# untitled.net
KiCad netlist of a schematic drawn in EAGLE
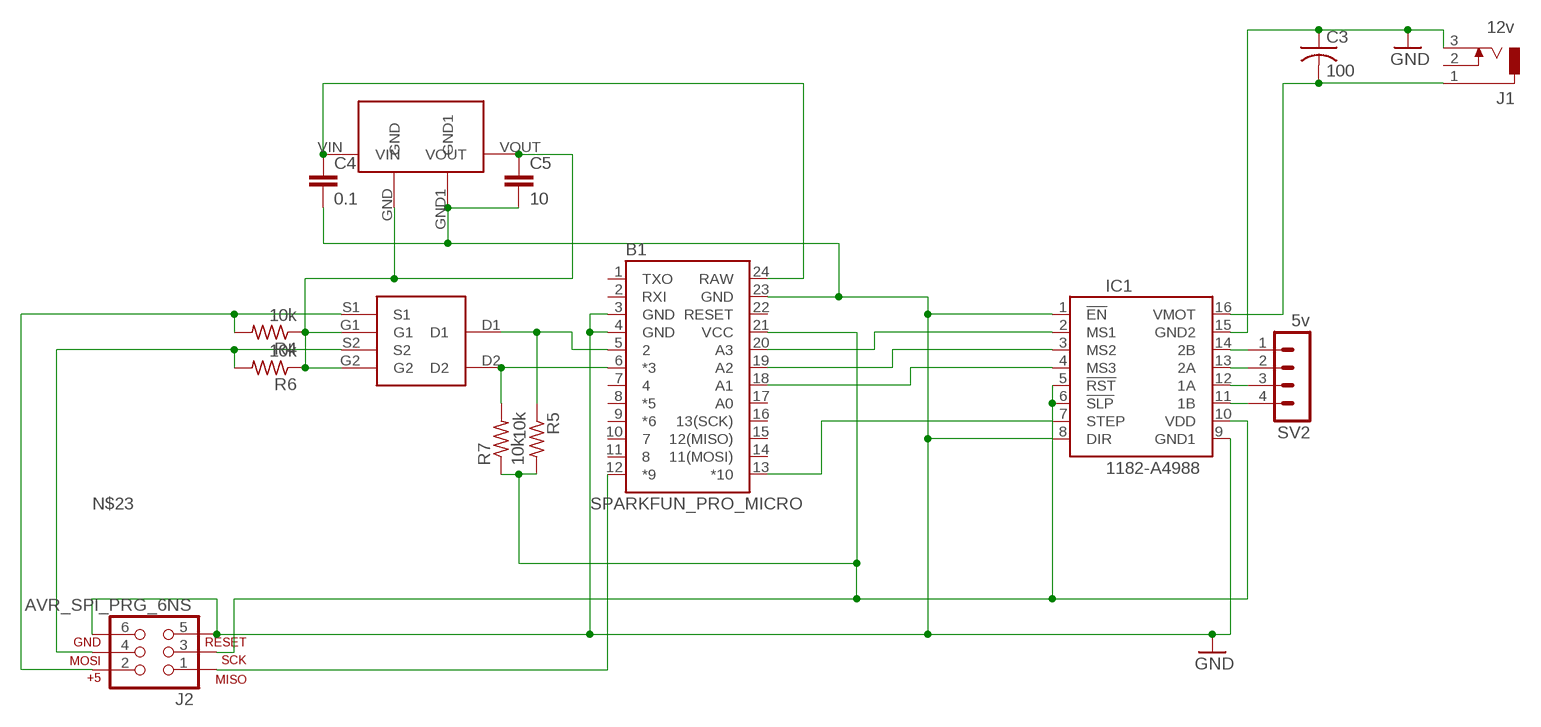
[diagram p0: schematic, sheet 1]

(export (version "E")
  (design (tool "Eeschema 10.0.6"))
  (components
    (comp (ref "B1")
      (value "SPARKFUN_PRO_MICRO")
      (footprint "eagle-import:SPARKFUN_PRO_MICRO")
      (libsource (lib "eagle-import") (part "SPARKFUN_PRO_MICRO"))
    )
    (comp (ref "C3")
      (value "100")
      (footprint "eagle-import:C050-075X075")
      (libsource (lib "eagle-import") (part "C-US050-075X075"))
    )
    (comp (ref "C4")
      (value "0.1")
      (footprint "eagle-import:0603-CAP")
      (libsource (lib "eagle-import") (part "CAP0603-CAP"))
    )
    (comp (ref "C5")
      (value "10")
      (footprint "eagle-import:0603-CAP")
      (libsource (lib "eagle-import") (part "CAP0603-CAP"))
    )
    (comp (ref "IC1")
      (value "1182-A4988")
      (footprint "eagle-import:A4988")
      (libsource (lib "eagle-import") (part "1182-A4988"))
    )
    (comp (ref "J1")
      (value "12v")
      (footprint "eagle-import:DCJ0303")
      (libsource (lib "eagle-import") (part "DCJ0303"))
    )
    (comp (ref "J2")
      (value "AVR_SPI_PRG_6NS")
      (footprint "eagle-import:2X3-NS")
      (libsource (lib "eagle-import") (part "AVR_SPI_PRG_6NS"))
    )
    (comp (ref "R4")
      (value "10k")
      (footprint "eagle-import:0207_10")
      (libsource (lib "eagle-import") (part "R-US_0207/10"))
    )
    (comp (ref "R5")
      (value "10k")
      (footprint "eagle-import:0207_10")
      (libsource (lib "eagle-import") (part "R-US_0207/10"))
    )
    (comp (ref "R6")
      (value "10k")
      (footprint "eagle-import:0207_10")
      (libsource (lib "eagle-import") (part "R-US_0207/10"))
    )
    (comp (ref "R7")
      (value "10k")
      (footprint "eagle-import:0207_10")
      (libsource (lib "eagle-import") (part "R-US_0207/10"))
    )
    (comp (ref "SV2")
      (value "5v")
      (footprint "eagle-import:MA04-1")
      (libsource (lib "eagle-import") (part "MA04-1"))
    )
    (comp (ref "U$2")
      (value "LD1117")
      (footprint "eagle-import:SOT223")
      (libsource (lib "eagle-import") (part "LD1117"))
    )
    (comp (ref "U$3")
      (value "BSS138")
      (footprint "eagle-import:SOT363")
      (libsource (lib "eagle-import") (part "BSS138"))
    )
  )
  (nets
    (net (code "1") (name "/N$23") (class "Default")
      (node (ref "J2") (pin "4") (pinfunction "4_4") (pintype "passive"))
      (node (ref "R6") (pin "2") (pinfunction "2_2") (pintype "passive"))
      (node (ref "U$3") (pin "S2") (pinfunction "S2_S2") (pintype "bidirectional"))
    )
    (net (code "2") (name "GND") (class "Default")
      (node (ref "B1") (pin "23") (pinfunction "GND_23") (pintype "power_in"))
      (node (ref "B1") (pin "3") (pinfunction "GND_3") (pintype "power_in"))
      (node (ref "B1") (pin "4") (pinfunction "GND_4") (pintype "power_in"))
      (node (ref "C3") (pin "1") (pinfunction "1_1") (pintype "passive"))
      (node (ref "C4") (pin "2") (pinfunction "2_2") (pintype "passive"))
      (node (ref "C5") (pin "2") (pinfunction "2_2") (pintype "passive"))
      (node (ref "IC1") (pin "1") (pinfunction "~{EN}_1") (pintype "passive"))
      (node (ref "IC1") (pin "15") (pinfunction "GND2_15") (pintype "power_in"))
      (node (ref "IC1") (pin "8") (pinfunction "DIR_8") (pintype "input"))
      (node (ref "IC1") (pin "9") (pinfunction "GND1_9") (pintype "power_in"))
      (node (ref "J1") (pin "3") (pinfunction "3_3") (pintype "passive"))
      (node (ref "J2") (pin "5") (pinfunction "5_5") (pintype "passive"))
      (node (ref "J2") (pin "6") (pinfunction "6_6") (pintype "passive"))
      (node (ref "U$2") (pin "GND1") (pinfunction "GND1_GND1") (pintype "bidirectional"))
    )
    (net (code "3") (name "Net-(B1-*3)") (class "Default")
      (node (ref "B1") (pin "6") (pinfunction "*3_6") (pintype "bidirectional"))
      (node (ref "R7") (pin "2") (pinfunction "2_2") (pintype "passive"))
      (node (ref "U$3") (pin "D2") (pinfunction "D2_D2") (pintype "bidirectional"))
    )
    (net (code "4") (name "Net-(B1-*9)") (class "Default")
      (node (ref "B1") (pin "12") (pinfunction "*9_12") (pintype "bidirectional"))
      (node (ref "J2") (pin "1") (pinfunction "1_1") (pintype "passive"))
    )
    (net (code "5") (name "Net-(B1-*10)") (class "Default")
      (node (ref "B1") (pin "13") (pinfunction "*10_13") (pintype "bidirectional"))
      (node (ref "IC1") (pin "7") (pinfunction "STEP_7") (pintype "input"))
    )
    (net (code "6") (name "Net-(B1-2)") (class "Default")
      (node (ref "B1") (pin "5") (pinfunction "2_5") (pintype "bidirectional"))
      (node (ref "R5") (pin "1") (pinfunction "1_1") (pintype "passive"))
      (node (ref "U$3") (pin "D1") (pinfunction "D1_D1") (pintype "bidirectional"))
    )
    (net (code "7") (name "Net-(B1-A1)") (class "Default")
      (node (ref "B1") (pin "18") (pinfunction "A1_18") (pintype "bidirectional"))
      (node (ref "IC1") (pin "4") (pinfunction "MS3_4") (pintype "passive"))
    )
    (net (code "8") (name "Net-(B1-A2)") (class "Default")
      (node (ref "B1") (pin "19") (pinfunction "A2_19") (pintype "bidirectional"))
      (node (ref "IC1") (pin "3") (pinfunction "MS2_3") (pintype "passive"))
    )
    (net (code "9") (name "Net-(B1-A3)") (class "Default")
      (node (ref "B1") (pin "20") (pinfunction "A3_20") (pintype "bidirectional"))
      (node (ref "IC1") (pin "2") (pinfunction "MS1_2") (pintype "passive"))
    )
    (net (code "10") (name "Net-(B1-RAW)") (class "Default")
      (node (ref "B1") (pin "24") (pinfunction "RAW_24") (pintype "power_in"))
      (node (ref "C4") (pin "1") (pinfunction "1_1") (pintype "passive"))
      (node (ref "U$2") (pin "VIN") (pinfunction "VIN_VIN") (pintype "bidirectional"))
    )
    (net (code "11") (name "Net-(B1-VCC)") (class "Default")
      (node (ref "B1") (pin "21") (pinfunction "VCC_21") (pintype "power_in"))
      (node (ref "IC1") (pin "10") (pinfunction "VDD_10") (pintype "power_in"))
      (node (ref "IC1") (pin "5") (pinfunction "~{RST}_5") (pintype "passive"))
      (node (ref "IC1") (pin "6") (pinfunction "~{SLP}_6") (pintype "passive"))
      (node (ref "J2") (pin "3") (pinfunction "3_3") (pintype "passive"))
      (node (ref "R5") (pin "2") (pinfunction "2_2") (pintype "passive"))
      (node (ref "R7") (pin "1") (pinfunction "1_1") (pintype "passive"))
    )
    (net (code "12") (name "Net-(C5-Pad1)") (class "Default")
      (node (ref "C5") (pin "1") (pinfunction "1_1") (pintype "passive"))
      (node (ref "R4") (pin "1") (pinfunction "1_1") (pintype "passive"))
      (node (ref "R6") (pin "1") (pinfunction "1_1") (pintype "passive"))
      (node (ref "U$2") (pin "GND") (pinfunction "GND_GND") (pintype "bidirectional"))
      (node (ref "U$2") (pin "VOUT") (pinfunction "VOUT_VOUT") (pintype "bidirectional"))
      (node (ref "U$3") (pin "G1") (pinfunction "G1_G1") (pintype "bidirectional"))
      (node (ref "U$3") (pin "G2") (pinfunction "G2_G2") (pintype "bidirectional"))
    )
    (net (code "13") (name "Net-(IC1-1A)") (class "Default")
      (node (ref "IC1") (pin "12") (pinfunction "1A_12") (pintype "output"))
      (node (ref "SV2") (pin "3") (pinfunction "3_3") (pintype "passive"))
    )
    (net (code "14") (name "Net-(IC1-1B)") (class "Default")
      (node (ref "IC1") (pin "11") (pinfunction "1B_11") (pintype "output"))
      (node (ref "SV2") (pin "4") (pinfunction "4_4") (pintype "passive"))
    )
    (net (code "15") (name "Net-(IC1-2A)") (class "Default")
      (node (ref "IC1") (pin "13") (pinfunction "2A_13") (pintype "output"))
      (node (ref "SV2") (pin "2") (pinfunction "2_2") (pintype "passive"))
    )
    (net (code "16") (name "Net-(IC1-2B)") (class "Default")
      (node (ref "IC1") (pin "14") (pinfunction "2B_14") (pintype "output"))
      (node (ref "SV2") (pin "1") (pinfunction "1_1") (pintype "passive"))
    )
    (net (code "17") (name "Net-(IC1-VMOT)") (class "Default")
      (node (ref "C3") (pin "2") (pinfunction "2_2") (pintype "passive"))
      (node (ref "IC1") (pin "16") (pinfunction "VMOT_16") (pintype "power_in"))
      (node (ref "J1") (pin "1") (pinfunction "1_1") (pintype "passive"))
    )
    (net (code "18") (name "Net-(J2-Pad2)") (class "Default")
      (node (ref "J2") (pin "2") (pinfunction "2_2") (pintype "passive"))
      (node (ref "R4") (pin "2") (pinfunction "2_2") (pintype "passive"))
      (node (ref "U$3") (pin "S1") (pinfunction "S1_S1") (pintype "bidirectional"))
    )
    (net (code "19") (name "unconnected-(B1-*5-Pad8)") (class "Default")
      (node (ref "B1") (pin "8") (pinfunction "*5_8") (pintype "bidirectional"))
    )
    (net (code "20") (name "unconnected-(B1-*6-Pad9)") (class "Default")
      (node (ref "B1") (pin "9") (pinfunction "*6_9") (pintype "bidirectional"))
    )
    (net (code "21") (name "unconnected-(B1-4-Pad7)") (class "Default")
      (node (ref "B1") (pin "7") (pinfunction "4_7") (pintype "bidirectional"))
    )
    (net (code "22") (name "unconnected-(B1-7-Pad10)") (class "Default")
      (node (ref "B1") (pin "10") (pinfunction "7_10") (pintype "bidirectional"))
    )
    (net (code "23") (name "unconnected-(B1-8-Pad11)") (class "Default")
      (node (ref "B1") (pin "11") (pinfunction "8_11") (pintype "bidirectional"))
    )
    (net (code "24") (name "unconnected-(B1-11(MOSI)-Pad14)") (class "Default")
      (node (ref "B1") (pin "14") (pinfunction "11(MOSI)_14") (pintype "bidirectional"))
    )
    (net (code "25") (name "unconnected-(B1-12(MISO)-Pad15)") (class "Default")
      (node (ref "B1") (pin "15") (pinfunction "12(MISO)_15") (pintype "bidirectional"))
    )
    (net (code "26") (name "unconnected-(B1-13(SCK)-Pad16)") (class "Default")
      (node (ref "B1") (pin "16") (pinfunction "13(SCK)_16") (pintype "bidirectional"))
    )
    (net (code "27") (name "unconnected-(B1-A0-Pad17)") (class "Default")
      (node (ref "B1") (pin "17") (pinfunction "A0_17") (pintype "bidirectional"))
    )
    (net (code "28") (name "unconnected-(B1-RESET-Pad22)") (class "Default")
      (node (ref "B1") (pin "22") (pinfunction "RESET_22") (pintype "bidirectional"))
    )
    (net (code "29") (name "unconnected-(B1-RXI-Pad2)") (class "Default")
      (node (ref "B1") (pin "2") (pinfunction "RXI_2") (pintype "bidirectional"))
    )
    (net (code "30") (name "unconnected-(B1-TXO-Pad1)") (class "Default")
      (node (ref "B1") (pin "1") (pinfunction "TXO_1") (pintype "bidirectional"))
    )
    (net (code "31") (name "unconnected-(J1-Pad2)") (class "Default")
      (node (ref "J1") (pin "2") (pinfunction "2_2") (pintype "passive"))
    )
  )
)
